# Balancing_Robot_1_2_Sensors.net
KiCad netlist of a schematic drawn in Altium Designer
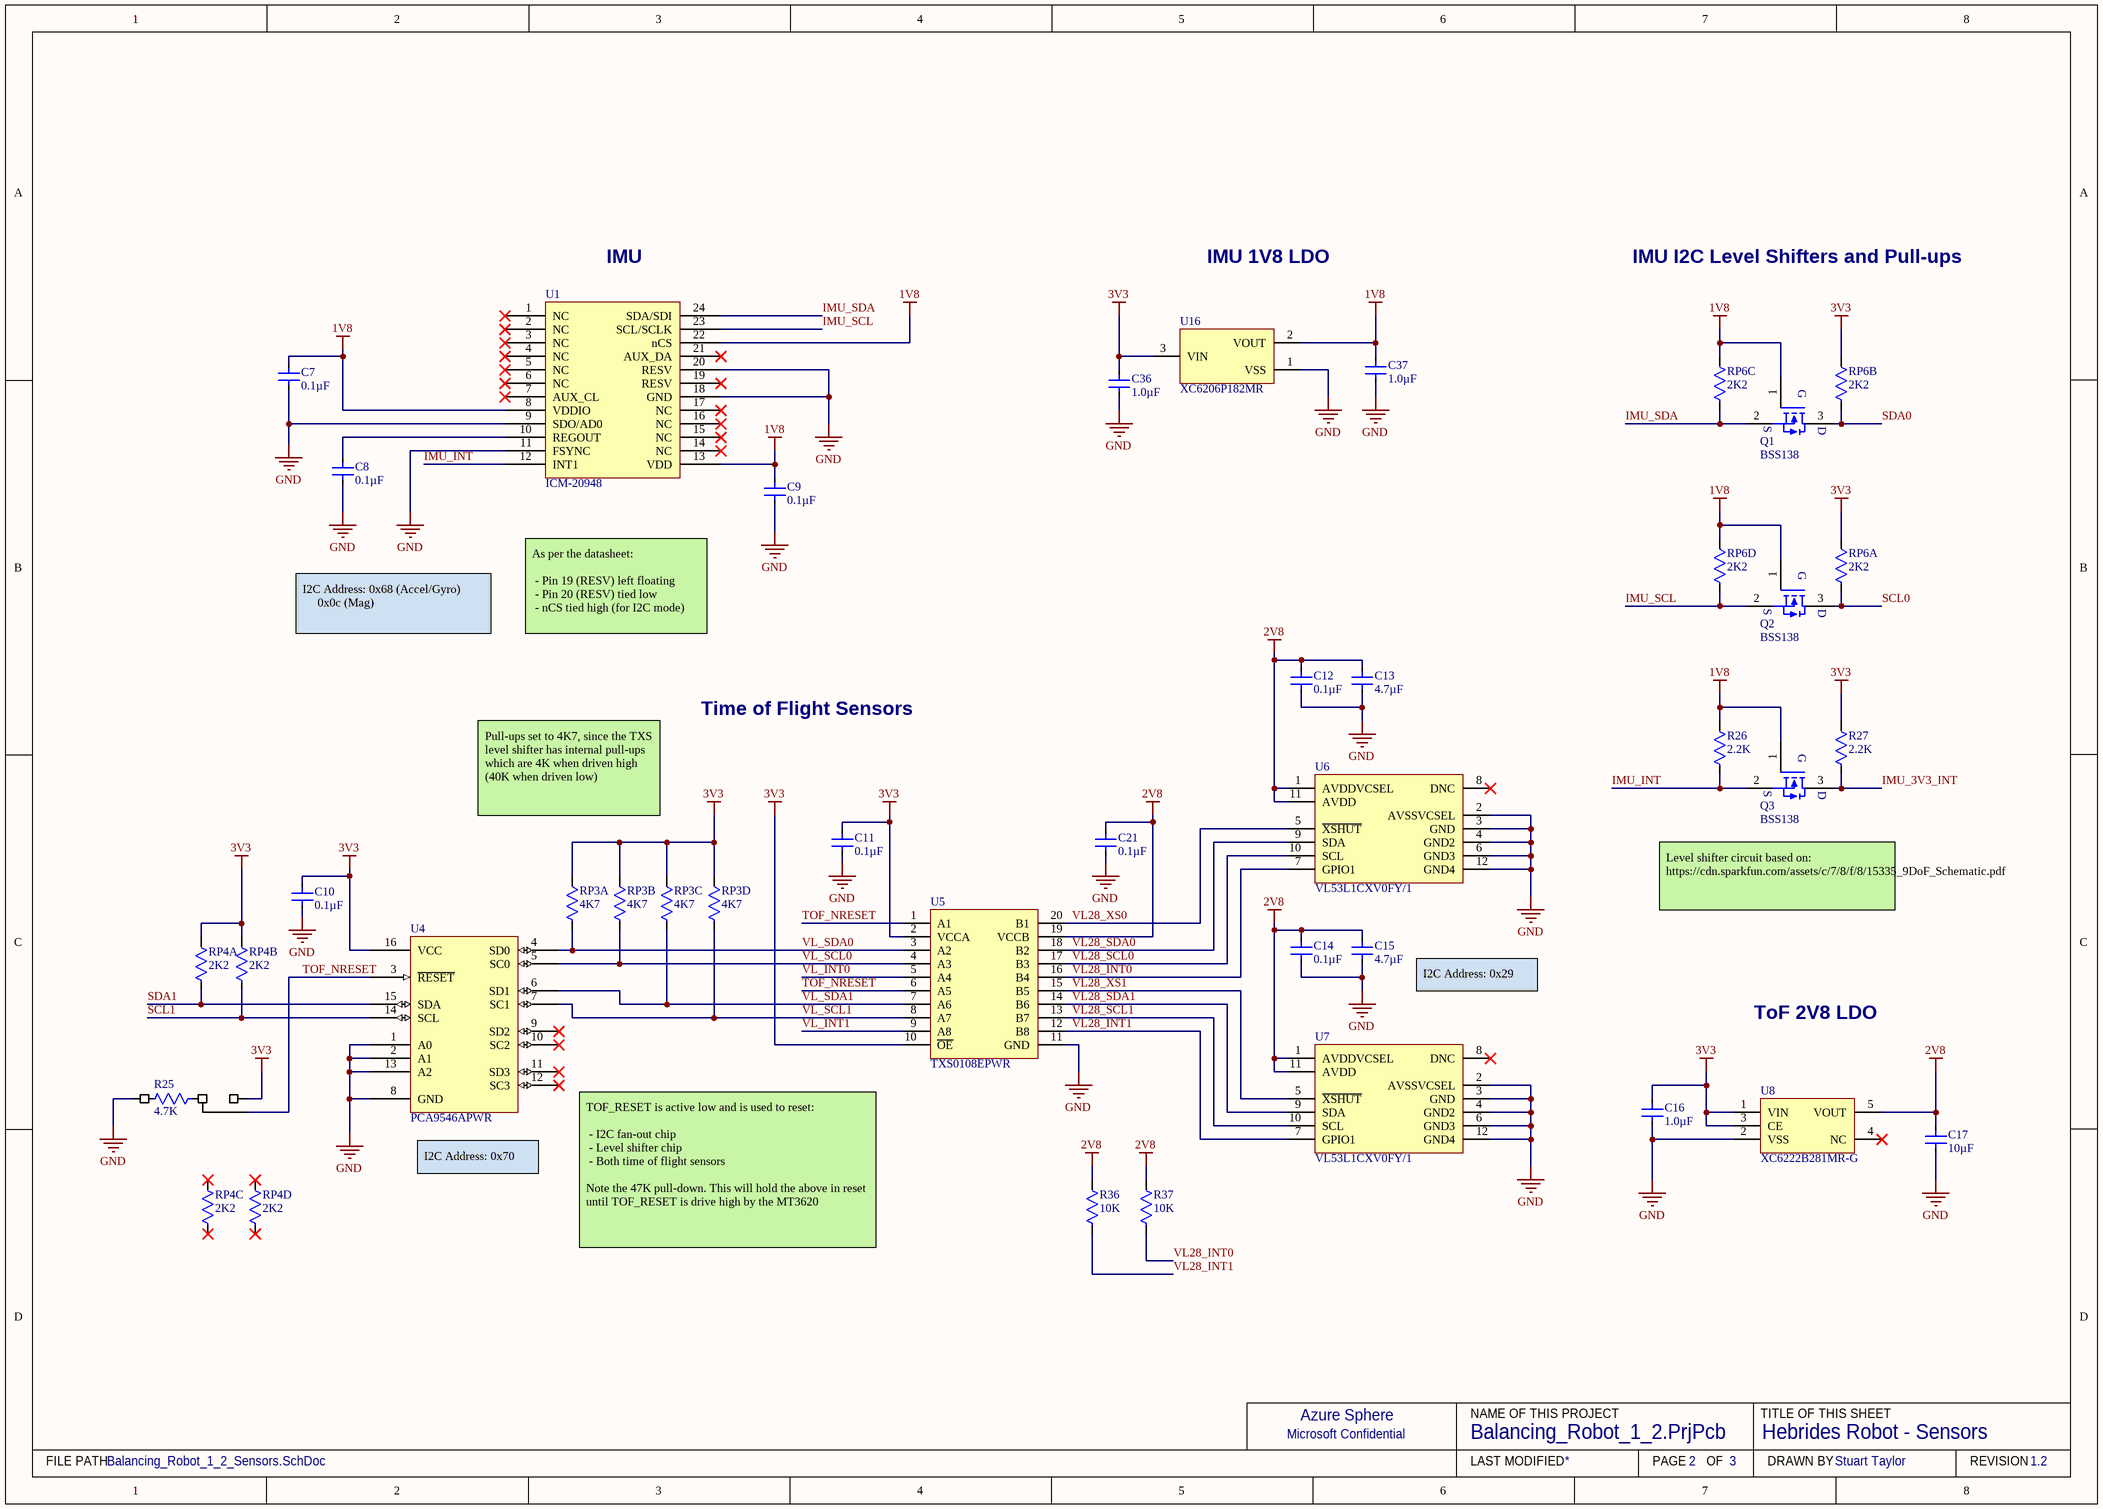
[diagram p0: Balancing_Robot_1_2_Sensors.SchDoc]

(export (version "E")
  (design (tool "Eeschema 10.0.6"))
  (components
    (comp (ref "C7")
      (value "0.1µF")
      (footprint "CAPC1005-EIA0402 0.55MM MED")
      (description "CAP CER 0.1UF 50V 10% X7R 0402")
      (fields
        (field (name "MANUFACTURER") "TDK Corporation")
        (field (name "MANUFACTURER PART NUMBER") "C1005X7R1H104K050BB")
        (field (name "CAPACITANCE") "0.1µF")
      )
      (libsource (lib "TDK_Capacitor_C_0402") (part "0.1µF 0402 X7R 50V"))
    )
    (comp (ref "C8")
      (value "0.1µF")
      (footprint "CAPC1005-EIA0402 0.55MM MED")
      (description "CAP CER 0.1UF 50V 10% X7R 0402")
      (fields
        (field (name "MANUFACTURER") "TDK Corporation")
        (field (name "MANUFACTURER PART NUMBER") "C1005X7R1H104K050BB")
        (field (name "CAPACITANCE") "0.1µF")
      )
      (libsource (lib "TDK_Capacitor_C_0402") (part "0.1µF 0402 X7R 50V"))
    )
    (comp (ref "C9")
      (value "0.1µF")
      (footprint "CAPC1005-EIA0402 0.55MM MED")
      (description "CAP CER 0.1UF 50V 10% X7R 0402")
      (fields
        (field (name "MANUFACTURER") "TDK Corporation")
        (field (name "MANUFACTURER PART NUMBER") "C1005X7R1H104K050BB")
        (field (name "CAPACITANCE") "0.1µF")
      )
      (libsource (lib "TDK_Capacitor_C_0402") (part "0.1µF 0402 X7R 50V"))
    )
    (comp (ref "C10")
      (value "0.1µF")
      (footprint "CAPC1005-EIA0402 0.55MM MED")
      (description "CAP CER 0.1UF 50V 10% X7R 0402")
      (fields
        (field (name "MANUFACTURER") "TDK Corporation")
        (field (name "MANUFACTURER PART NUMBER") "C1005X7R1H104K050BB")
        (field (name "CAPACITANCE") "0.1µF")
      )
      (libsource (lib "TDK_Capacitor_C_0402") (part "0.1µF 0402 X7R 50V"))
    )
    (comp (ref "C11")
      (value "0.1µF")
      (footprint "CAPC1005-EIA0402 0.55MM MED")
      (description "CAP CER 0.1UF 50V 10% X7R 0402")
      (fields
        (field (name "MANUFACTURER") "TDK Corporation")
        (field (name "MANUFACTURER PART NUMBER") "C1005X7R1H104K050BB")
        (field (name "CAPACITANCE") "0.1µF")
      )
      (libsource (lib "TDK_Capacitor_C_0402") (part "0.1µF 0402 X7R 50V"))
    )
    (comp (ref "C12")
      (value "0.1µF")
      (footprint "CAPC1005-EIA0402 0.55MM MED")
      (description "CAP CER 0.1UF 50V 10% X7R 0402")
      (fields
        (field (name "MANUFACTURER") "TDK Corporation")
        (field (name "MANUFACTURER PART NUMBER") "C1005X7R1H104K050BB")
        (field (name "CAPACITANCE") "0.1µF")
      )
      (libsource (lib "TDK_Capacitor_C_0402") (part "0.1µF 0402 X7R 50V"))
    )
    (comp (ref "C13")
      (value "C1005X5R1A475K050BC")
      (footprint "CAPC1005-EIA0402 0.55MM MED")
      (description "CAP CER 4.7UF 10V 10% X5R 0402")
      (fields
        (field (name "MANUFACTURER") "TDK Corporation")
        (field (name "TOLERANCE") "±10%")
        (field (name "CAPACITANCE") "4.7µF")
      )
      (libsource (lib "TDK_Capacitor_C_0402") (part "4.7µF 0402 X5R 10V"))
    )
    (comp (ref "C14")
      (value "0.1µF")
      (footprint "CAPC1005-EIA0402 0.55MM MED")
      (description "CAP CER 0.1UF 50V 10% X7R 0402")
      (fields
        (field (name "MANUFACTURER") "TDK Corporation")
        (field (name "MANUFACTURER PART NUMBER") "C1005X7R1H104K050BB")
        (field (name "CAPACITANCE") "0.1µF")
      )
      (libsource (lib "TDK_Capacitor_C_0402") (part "0.1µF 0402 X7R 50V"))
    )
    (comp (ref "C15")
      (value "C1005X5R1A475K050BC")
      (footprint "CAPC1005-EIA0402 0.55MM MED")
      (description "CAP CER 4.7UF 10V 10% X5R 0402")
      (fields
        (field (name "MANUFACTURER") "TDK Corporation")
        (field (name "TOLERANCE") "±10%")
        (field (name "CAPACITANCE") "4.7µF")
      )
      (libsource (lib "TDK_Capacitor_C_0402") (part "4.7µF 0402 X5R 10V"))
    )
    (comp (ref "C16")
      (value "C1005X5R1V105K050BC")
      (footprint "CAPC1005-EIA0402 0.55MM MED")
      (description "CAP CER 1UF 35V 10% X5R 0402")
      (fields
        (field (name "MANUFACTURER") "TDK Corporation")
        (field (name "TOLERANCE") "±10%")
        (field (name "CAPACITANCE") "1.0µF")
      )
      (libsource (lib "TDK_Capacitor_C_0402") (part "1.0µF 0402 X5R 35V"))
    )
    (comp (ref "C17")
      (value "10µF")
      (footprint "CAPC1005-EIA0402 0.55MM MED")
      (description "CAP CER 10UF 6.3V 20% X5R 0402")
      (fields
        (field (name "MANUFACTURER") "TDK Corporation")
        (field (name "MANUFACTURER PART NUMBER") "C1005X5R0J106M050BC")
        (field (name "CAPACITANCE") "10µF")
      )
      (libsource (lib "TDK_Capacitor_C_0402") (part "10µF 0402 X5R 6.3V"))
    )
    (comp (ref "C21")
      (value "0.1µF")
      (footprint "CAPC1005-EIA0402 0.55MM MED")
      (description "CAP CER 0.1UF 50V 10% X7R 0402")
      (fields
        (field (name "MANUFACTURER") "TDK Corporation")
        (field (name "MANUFACTURER PART NUMBER") "C1005X7R1H104K050BB")
        (field (name "CAPACITANCE") "0.1µF")
      )
      (libsource (lib "TDK_Capacitor_C_0402") (part "0.1µF 0402 X7R 50V"))
    )
    (comp (ref "C36")
      (value "C1005X5R1V105K050BC")
      (footprint "CAPC1005-EIA0402 0.55MM MED")
      (description "CAP CER 1UF 35V 10% X5R 0402")
      (fields
        (field (name "MANUFACTURER") "TDK Corporation")
        (field (name "TOLERANCE") "±10%")
        (field (name "CAPACITANCE") "1.0µF")
      )
      (libsource (lib "TDK_Capacitor_C_0402") (part "1.0µF 0402 X5R 35V"))
    )
    (comp (ref "C37")
      (value "C1005X5R1V105K050BC")
      (footprint "CAPC1005-EIA0402 0.55MM MED")
      (description "CAP CER 1UF 35V 10% X5R 0402")
      (fields
        (field (name "MANUFACTURER") "TDK Corporation")
        (field (name "TOLERANCE") "±10%")
        (field (name "CAPACITANCE") "1.0µF")
      )
      (libsource (lib "TDK_Capacitor_C_0402") (part "1.0µF 0402 X5R 35V"))
    )
    (comp (ref "Q1")
      (value "BSS138")
      (footprint "TOREX-SOT23-3")
      (description "MOSFET N-CH 50V 220MA SOT-23")
      (fields (field (name "MANUFACTURER") "Micross"))
      (libsource (lib "Fairchild") (part "BSS138"))
    )
    (comp (ref "Q2")
      (value "BSS138")
      (footprint "TOREX-SOT23-3")
      (description "MOSFET N-CH 50V 220MA SOT-23")
      (fields (field (name "MANUFACTURER") "Micross"))
      (libsource (lib "Fairchild") (part "BSS138"))
    )
    (comp (ref "Q3")
      (value "BSS138")
      (footprint "TOREX-SOT23-3")
      (description "MOSFET N-CH 50V 220MA SOT-23")
      (fields (field (name "MANUFACTURER") "Micross"))
      (libsource (lib "Fairchild") (part "BSS138"))
    )
    (comp (ref "R25")
      (value "4.7K")
      (footprint "THREE-WAY-0402-NO-SHORT")
      (description "RES SMD 4.7K JUMPER 1/10W 0402")
      (fields
        (field (name "MANUFACTURER") "Panasonic Electronic Components")
        (field (name "MANUFACTURER PART NUMBER") "ERJ-2RKF4701X")
      )
      (libsource (lib "generic-res") (part "THREE-WAY-4K7-0402-NO-SHORT"))
    )
    (comp (ref "R26")
      (value "2.2K")
      (footprint "RES 0402 MEDIUM DENSITY")
      (description "RES 2.2K OHM 1/10W 1% 0402 SMD")
      (fields
        (field (name "MANUFACTURER") "Panasonic Electronic Components")
        (field (name "MANUFACTURER PART NUMBER") "ERJ-2RKF2201X")
        (field (name "RESISTANCE (OHMS)") "2.2K")
      )
      (libsource (lib "Panasonic_Resistor_ERJ2R") (part "2.2K"))
    )
    (comp (ref "R27")
      (value "2.2K")
      (footprint "RES 0402 MEDIUM DENSITY")
      (description "RES 2.2K OHM 1/10W 1% 0402 SMD")
      (fields
        (field (name "MANUFACTURER") "Panasonic Electronic Components")
        (field (name "MANUFACTURER PART NUMBER") "ERJ-2RKF2201X")
        (field (name "RESISTANCE (OHMS)") "2.2K")
      )
      (libsource (lib "Panasonic_Resistor_ERJ2R") (part "2.2K"))
    )
    (comp (ref "R36")
      (value "10K")
      (footprint "RES 0402 MEDIUM DENSITY")
      (description "RES 10K OHM 1/10W 1% 0402 SMD")
      (fields
        (field (name "MANUFACTURER") "Panasonic Electronic Components")
        (field (name "MANUFACTURER PART NUMBER") "ERJ-2RKF1002X")
        (field (name "RESISTANCE (OHMS)") "10K")
      )
      (libsource (lib "Panasonic_Resistor_ERJ2R") (part "10K"))
    )
    (comp (ref "R37")
      (value "10K")
      (footprint "RES 0402 MEDIUM DENSITY")
      (description "RES 10K OHM 1/10W 1% 0402 SMD")
      (fields
        (field (name "MANUFACTURER") "Panasonic Electronic Components")
        (field (name "MANUFACTURER PART NUMBER") "ERJ-2RKF1002X")
        (field (name "RESISTANCE (OHMS)") "10K")
      )
      (libsource (lib "Panasonic_Resistor_ERJ2R") (part "10K"))
    )
    (comp (ref "RP3")
      (value "4K7")
      (footprint "EXB-N8V")
      (fields
        (field (name "MANUFACTURER") "Panasonic / Panasonic ECG")
        (field (name "MANUFACTURER PART NUMBER") "EXB-N8V472JX")
      )
      (libsource (lib "Panasonic") (part "EXB-N8V472JX"))
    )
    (comp (ref "RP4")
      (value "2K2")
      (footprint "EXB-N8V")
      (fields
        (field (name "MANUFACTURER") "Panasonic / Panasonic ECG")
        (field (name "MANUFACTURER PART NUMBER") "EXB-N8V222JX")
      )
      (libsource (lib "Panasonic") (part "EXB-N8V222JX"))
    )
    (comp (ref "RP6")
      (value "2K2")
      (footprint "EXB-N8V")
      (fields
        (field (name "MANUFACTURER") "Panasonic / Panasonic ECG")
        (field (name "MANUFACTURER PART NUMBER") "EXB-N8V222JX")
      )
      (libsource (lib "Panasonic") (part "EXB-N8V222JX"))
    )
    (comp (ref "U1")
      (value "ICM-20948")
      (footprint "ICM_20948")
      (description "9-axis IMU")
      (fields (field (name "MANUFACTURER") "TDK"))
      (libsource (lib "InvenSense") (part "ICM-20948"))
    )
    (comp (ref "U4")
      (value "PCA9546APWR")
      (footprint "PCA9546APWR")
      (fields (field (name "MANUFACTURER") "Texas Instruments"))
      (libsource (lib "TexasInstruments") (part "PCA9546APWR"))
    )
    (comp (ref "U5")
      (value "TXS0108EPWR")
      (footprint "TXS0108EPWR")
      (description "IC 8BIT NON-INV TRANSLTR 20TSSOP")
      (fields (field (name "MANUFACTURER") "Texas Instruments"))
      (libsource (lib "TexasInstruments") (part "TXS0108EPWR"))
    )
    (comp (ref "U6")
      (value "VL53L1CXV0FY/1")
      (footprint "VL53L1X")
      (description "OPTICAL LGA12 4.9X2")
      (fields (field (name "MANUFACTURER") "STMicroelectronics"))
      (libsource (lib "ST") (part "VL53L1CXV0FY/1"))
    )
    (comp (ref "U7")
      (value "VL53L1CXV0FY/1")
      (footprint "VL53L1X")
      (description "OPTICAL LGA12 4.9X2")
      (fields (field (name "MANUFACTURER") "STMicroelectronics"))
      (libsource (lib "ST") (part "VL53L1CXV0FY/1"))
    )
    (comp (ref "U8")
      (value "XC6222B281MR-G")
      (footprint "SOT25")
      (description "Reverse Current Protection, 700mA High Speed LDO Regulator")
      (fields (field (name "MANUFACTURER") "Torex"))
      (libsource (lib "Torex") (part "XC6222B281MR-G"))
    )
    (comp (ref "U16")
      (value "XC6206P182MR")
      (footprint "TOREX-SOT23-3")
      (fields (field (name "MANUFACTURER") "Torex Semiconductor"))
      (libsource (lib "Torex") (part "XC6206P182MR"))
    )
  )
  (nets
    (net (code "1") (name "/IMU_3V3_INT") (class "Default")
      (node (ref "Q3") (pin "3") (pinfunction "D_3") (pintype "passive"))
      (node (ref "R27") (pin "2") (pinfunction "2_2") (pintype "passive"))
    )
    (net (code "2") (name "/IMU_INT") (class "Default")
      (node (ref "Q3") (pin "2") (pinfunction "S_2") (pintype "passive"))
      (node (ref "R26") (pin "2") (pinfunction "2_2") (pintype "passive"))
      (node (ref "U1") (pin "12") (pinfunction "INT1_12") (pintype "passive"))
    )
    (net (code "3") (name "/IMU_SCL") (class "Default")
      (node (ref "Q2") (pin "2") (pinfunction "S_2") (pintype "passive"))
      (node (ref "RP6") (pin "7") (pinfunction "7_7") (pintype "passive"))
      (node (ref "U1") (pin "23") (pinfunction "SCL/SCLK_23") (pintype "passive"))
    )
    (net (code "4") (name "/IMU_SDA") (class "Default")
      (node (ref "Q1") (pin "2") (pinfunction "S_2") (pintype "passive"))
      (node (ref "RP6") (pin "5") (pinfunction "5_5") (pintype "passive"))
      (node (ref "U1") (pin "24") (pinfunction "SDA/SDI_24") (pintype "passive"))
    )
    (net (code "5") (name "/SCL0") (class "Default")
      (node (ref "Q2") (pin "3") (pinfunction "D_3") (pintype "passive"))
      (node (ref "RP6") (pin "1") (pinfunction "1_1") (pintype "passive"))
    )
    (net (code "6") (name "/SCL1") (class "Default")
      (node (ref "RP4") (pin "3") (pinfunction "3_3") (pintype "passive"))
      (node (ref "U4") (pin "14") (pinfunction "SCL_14") (pintype "bidirectional"))
    )
    (net (code "7") (name "/SDA0") (class "Default")
      (node (ref "Q1") (pin "3") (pinfunction "D_3") (pintype "passive"))
      (node (ref "RP6") (pin "3") (pinfunction "3_3") (pintype "passive"))
    )
    (net (code "8") (name "/SDA1") (class "Default")
      (node (ref "RP4") (pin "1") (pinfunction "1_1") (pintype "passive"))
      (node (ref "U4") (pin "15") (pinfunction "SDA_15") (pintype "bidirectional"))
    )
    (net (code "9") (name "/TOF_NRESET") (class "Default")
      (node (ref "R25") (pin "2") (pinfunction "2_2") (pintype "passive"))
      (node (ref "U4") (pin "3") (pinfunction "~{RESET}_3") (pintype "input"))
      (node (ref "U5") (pin "1") (pinfunction "A1_1") (pintype "passive"))
      (node (ref "U5") (pin "6") (pinfunction "A5_6") (pintype "passive"))
    )
    (net (code "10") (name "/VL28_INT0") (class "Default")
      (node (ref "R37") (pin "2") (pinfunction "2_2") (pintype "passive"))
      (node (ref "U5") (pin "16") (pinfunction "B4_16") (pintype "passive"))
      (node (ref "U6") (pin "7") (pinfunction "GPIO1_7") (pintype "passive"))
    )
    (net (code "11") (name "/VL28_INT1") (class "Default")
      (node (ref "R36") (pin "2") (pinfunction "2_2") (pintype "passive"))
      (node (ref "U5") (pin "12") (pinfunction "B8_12") (pintype "passive"))
      (node (ref "U7") (pin "7") (pinfunction "GPIO1_7") (pintype "passive"))
    )
    (net (code "12") (name "/VL28_SCL0") (class "Default")
      (node (ref "U5") (pin "17") (pinfunction "B3_17") (pintype "passive"))
      (node (ref "U6") (pin "10") (pinfunction "SCL_10") (pintype "passive"))
    )
    (net (code "13") (name "/VL28_SCL1") (class "Default")
      (node (ref "U5") (pin "13") (pinfunction "B7_13") (pintype "passive"))
      (node (ref "U7") (pin "10") (pinfunction "SCL_10") (pintype "passive"))
    )
    (net (code "14") (name "/VL28_SDA0") (class "Default")
      (node (ref "U5") (pin "18") (pinfunction "B2_18") (pintype "passive"))
      (node (ref "U6") (pin "9") (pinfunction "SDA_9") (pintype "passive"))
    )
    (net (code "15") (name "/VL28_SDA1") (class "Default")
      (node (ref "U5") (pin "14") (pinfunction "B6_14") (pintype "passive"))
      (node (ref "U7") (pin "9") (pinfunction "SDA_9") (pintype "passive"))
    )
    (net (code "16") (name "/VL28_XS0") (class "Default")
      (node (ref "U5") (pin "20") (pinfunction "B1_20") (pintype "passive"))
      (node (ref "U6") (pin "5") (pinfunction "~{XSHUT}_5") (pintype "passive"))
    )
    (net (code "17") (name "/VL28_XS1") (class "Default")
      (node (ref "U5") (pin "15") (pinfunction "B5_15") (pintype "passive"))
      (node (ref "U7") (pin "5") (pinfunction "~{XSHUT}_5") (pintype "passive"))
    )
    (net (code "18") (name "/VL_INT0") (class "Default")
      (node (ref "U5") (pin "5") (pinfunction "A4_5") (pintype "passive"))
    )
    (net (code "19") (name "/VL_INT1") (class "Default")
      (node (ref "U5") (pin "9") (pinfunction "A8_9") (pintype "passive"))
    )
    (net (code "20") (name "/VL_SCL0") (class "Default")
      (node (ref "RP3") (pin "3") (pinfunction "3_3") (pintype "passive"))
      (node (ref "U4") (pin "5") (pinfunction "SC0_5") (pintype "bidirectional"))
      (node (ref "U5") (pin "4") (pinfunction "A3_4") (pintype "passive"))
    )
    (net (code "21") (name "/VL_SCL1") (class "Default")
      (node (ref "RP3") (pin "7") (pinfunction "7_7") (pintype "passive"))
      (node (ref "U4") (pin "7") (pinfunction "SC1_7") (pintype "bidirectional"))
      (node (ref "U5") (pin "8") (pinfunction "A7_8") (pintype "passive"))
    )
    (net (code "22") (name "/VL_SDA0") (class "Default")
      (node (ref "RP3") (pin "1") (pinfunction "1_1") (pintype "passive"))
      (node (ref "U4") (pin "4") (pinfunction "SD0_4") (pintype "bidirectional"))
      (node (ref "U5") (pin "3") (pinfunction "A2_3") (pintype "passive"))
    )
    (net (code "23") (name "/VL_SDA1") (class "Default")
      (node (ref "RP3") (pin "5") (pinfunction "5_5") (pintype "passive"))
      (node (ref "U4") (pin "6") (pinfunction "SD1_6") (pintype "bidirectional"))
      (node (ref "U5") (pin "7") (pinfunction "A6_7") (pintype "passive"))
    )
    (net (code "24") (name "1V8") (class "Default")
      (node (ref "C37") (pin "2") (pinfunction "2_2") (pintype "passive"))
      (node (ref "C7") (pin "2") (pinfunction "2_2") (pintype "passive"))
      (node (ref "C9") (pin "2") (pinfunction "2_2") (pintype "passive"))
      (node (ref "Q1") (pin "1") (pinfunction "G_1") (pintype "passive"))
      (node (ref "Q2") (pin "1") (pinfunction "G_1") (pintype "passive"))
      (node (ref "Q3") (pin "1") (pinfunction "G_1") (pintype "passive"))
      (node (ref "R26") (pin "1") (pinfunction "1_1") (pintype "passive"))
      (node (ref "RP6") (pin "6") (pinfunction "6_6") (pintype "passive"))
      (node (ref "RP6") (pin "8") (pinfunction "8_8") (pintype "passive"))
      (node (ref "U1") (pin "13") (pinfunction "VDD_13") (pintype "passive"))
      (node (ref "U1") (pin "22") (pinfunction "nCS_22") (pintype "passive"))
      (node (ref "U1") (pin "8") (pinfunction "VDDIO_8") (pintype "passive"))
      (node (ref "U16") (pin "2") (pinfunction "VOUT_2") (pintype "passive"))
    )
    (net (code "25") (name "2V8") (class "Default")
      (node (ref "C12") (pin "2") (pinfunction "2_2") (pintype "passive"))
      (node (ref "C13") (pin "2") (pinfunction "2_2") (pintype "passive"))
      (node (ref "C14") (pin "2") (pinfunction "2_2") (pintype "passive"))
      (node (ref "C15") (pin "2") (pinfunction "2_2") (pintype "passive"))
      (node (ref "C17") (pin "2") (pinfunction "2_2") (pintype "passive"))
      (node (ref "C21") (pin "2") (pinfunction "2_2") (pintype "passive"))
      (node (ref "R36") (pin "1") (pinfunction "1_1") (pintype "passive"))
      (node (ref "R37") (pin "1") (pinfunction "1_1") (pintype "passive"))
      (node (ref "U5") (pin "19") (pinfunction "VCCB_19") (pintype "passive"))
      (node (ref "U6") (pin "1") (pinfunction "AVDDVCSEL_1") (pintype "passive"))
      (node (ref "U6") (pin "11") (pinfunction "AVDD_11") (pintype "passive"))
      (node (ref "U7") (pin "1") (pinfunction "AVDDVCSEL_1") (pintype "passive"))
      (node (ref "U7") (pin "11") (pinfunction "AVDD_11") (pintype "passive"))
      (node (ref "U8") (pin "5") (pinfunction "VOUT_5") (pintype "passive"))
    )
    (net (code "26") (name "3V3") (class "Default")
      (node (ref "C10") (pin "2") (pinfunction "2_2") (pintype "passive"))
      (node (ref "C11") (pin "2") (pinfunction "2_2") (pintype "passive"))
      (node (ref "C16") (pin "2") (pinfunction "2_2") (pintype "passive"))
      (node (ref "C36") (pin "2") (pinfunction "2_2") (pintype "passive"))
      (node (ref "R25") (pin "3") (pinfunction "3_3") (pintype "passive"))
      (node (ref "R27") (pin "1") (pinfunction "1_1") (pintype "passive"))
      (node (ref "RP3") (pin "2") (pinfunction "2_2") (pintype "passive"))
      (node (ref "RP3") (pin "4") (pinfunction "4_4") (pintype "passive"))
      (node (ref "RP3") (pin "6") (pinfunction "6_6") (pintype "passive"))
      (node (ref "RP3") (pin "8") (pinfunction "8_8") (pintype "passive"))
      (node (ref "RP4") (pin "2") (pinfunction "2_2") (pintype "passive"))
      (node (ref "RP4") (pin "4") (pinfunction "4_4") (pintype "passive"))
      (node (ref "RP6") (pin "2") (pinfunction "2_2") (pintype "passive"))
      (node (ref "RP6") (pin "4") (pinfunction "4_4") (pintype "passive"))
      (node (ref "U16") (pin "3") (pinfunction "VIN_3") (pintype "passive"))
      (node (ref "U4") (pin "16") (pinfunction "VCC_16") (pintype "power_in"))
      (node (ref "U5") (pin "10") (pinfunction "~{OE}_10") (pintype "passive"))
      (node (ref "U5") (pin "2") (pinfunction "VCCA_2") (pintype "passive"))
      (node (ref "U8") (pin "1") (pinfunction "VIN_1") (pintype "passive"))
      (node (ref "U8") (pin "3") (pinfunction "CE_3") (pintype "passive"))
    )
    (net (code "27") (name "GND") (class "Default")
      (node (ref "C10") (pin "1") (pinfunction "1_1") (pintype "passive"))
      (node (ref "C11") (pin "1") (pinfunction "1_1") (pintype "passive"))
      (node (ref "C12") (pin "1") (pinfunction "1_1") (pintype "passive"))
      (node (ref "C13") (pin "1") (pinfunction "1_1") (pintype "passive"))
      (node (ref "C14") (pin "1") (pinfunction "1_1") (pintype "passive"))
      (node (ref "C15") (pin "1") (pinfunction "1_1") (pintype "passive"))
      (node (ref "C16") (pin "1") (pinfunction "1_1") (pintype "passive"))
      (node (ref "C17") (pin "1") (pinfunction "1_1") (pintype "passive"))
      (node (ref "C21") (pin "1") (pinfunction "1_1") (pintype "passive"))
      (node (ref "C36") (pin "1") (pinfunction "1_1") (pintype "passive"))
      (node (ref "C37") (pin "1") (pinfunction "1_1") (pintype "passive"))
      (node (ref "C7") (pin "1") (pinfunction "1_1") (pintype "passive"))
      (node (ref "C8") (pin "1") (pinfunction "1_1") (pintype "passive"))
      (node (ref "C9") (pin "1") (pinfunction "1_1") (pintype "passive"))
      (node (ref "R25") (pin "1") (pinfunction "1_1") (pintype "passive"))
      (node (ref "U1") (pin "11") (pinfunction "FSYNC_11") (pintype "passive"))
      (node (ref "U1") (pin "18") (pinfunction "GND_18") (pintype "passive"))
      (node (ref "U1") (pin "20") (pinfunction "RESV_20") (pintype "passive"))
      (node (ref "U1") (pin "9") (pinfunction "SDO/AD0_9") (pintype "passive"))
      (node (ref "U16") (pin "1") (pinfunction "VSS_1") (pintype "passive"))
      (node (ref "U4") (pin "1") (pinfunction "A0_1") (pintype "power_in"))
      (node (ref "U4") (pin "13") (pinfunction "A2_13") (pintype "power_in"))
      (node (ref "U4") (pin "2") (pinfunction "A1_2") (pintype "power_in"))
      (node (ref "U4") (pin "8") (pinfunction "GND_8") (pintype "power_in"))
      (node (ref "U5") (pin "11") (pinfunction "GND_11") (pintype "passive"))
      (node (ref "U6") (pin "12") (pinfunction "GND4_12") (pintype "passive"))
      (node (ref "U6") (pin "2") (pinfunction "AVSSVCSEL_2") (pintype "passive"))
      (node (ref "U6") (pin "3") (pinfunction "GND_3") (pintype "passive"))
      (node (ref "U6") (pin "4") (pinfunction "GND2_4") (pintype "passive"))
      (node (ref "U6") (pin "6") (pinfunction "GND3_6") (pintype "passive"))
      (node (ref "U7") (pin "12") (pinfunction "GND4_12") (pintype "passive"))
      (node (ref "U7") (pin "2") (pinfunction "AVSSVCSEL_2") (pintype "passive"))
      (node (ref "U7") (pin "3") (pinfunction "GND_3") (pintype "passive"))
      (node (ref "U7") (pin "4") (pinfunction "GND2_4") (pintype "passive"))
      (node (ref "U7") (pin "6") (pinfunction "GND3_6") (pintype "passive"))
      (node (ref "U8") (pin "2") (pinfunction "VSS_2") (pintype "passive"))
    )
    (net (code "28") (name "Net-(U1-REGOUT)") (class "Default")
      (node (ref "C8") (pin "2") (pinfunction "2_2") (pintype "passive"))
      (node (ref "U1") (pin "10") (pinfunction "REGOUT_10") (pintype "passive"))
    )
    (net (code "29") (name "unconnected-(RP4-Pad5)") (class "Default")
      (node (ref "RP4") (pin "5") (pinfunction "5_5") (pintype "passive+no_connect"))
    )
    (net (code "30") (name "unconnected-(RP4-Pad6)") (class "Default")
      (node (ref "RP4") (pin "6") (pinfunction "6_6") (pintype "passive+no_connect"))
    )
    (net (code "31") (name "unconnected-(RP4-Pad7)") (class "Default")
      (node (ref "RP4") (pin "7") (pinfunction "7_7") (pintype "passive+no_connect"))
    )
    (net (code "32") (name "unconnected-(RP4-Pad8)") (class "Default")
      (node (ref "RP4") (pin "8") (pinfunction "8_8") (pintype "passive+no_connect"))
    )
    (net (code "33") (name "unconnected-(U1-AUX_CL-Pad7)") (class "Default")
      (node (ref "U1") (pin "7") (pinfunction "AUX_CL_7") (pintype "passive+no_connect"))
    )
    (net (code "34") (name "unconnected-(U1-AUX_DA-Pad21)") (class "Default")
      (node (ref "U1") (pin "21") (pinfunction "AUX_DA_21") (pintype "passive+no_connect"))
    )
    (net (code "35") (name "unconnected-(U1-NC-Pad1)") (class "Default")
      (node (ref "U1") (pin "1") (pinfunction "NC_1") (pintype "passive+no_connect"))
    )
    (net (code "36") (name "unconnected-(U1-NC-Pad2)") (class "Default")
      (node (ref "U1") (pin "2") (pinfunction "NC_2") (pintype "passive+no_connect"))
    )
    (net (code "37") (name "unconnected-(U1-NC-Pad3)") (class "Default")
      (node (ref "U1") (pin "3") (pinfunction "NC_3") (pintype "passive+no_connect"))
    )
    (net (code "38") (name "unconnected-(U1-NC-Pad4)") (class "Default")
      (node (ref "U1") (pin "4") (pinfunction "NC_4") (pintype "passive+no_connect"))
    )
    (net (code "39") (name "unconnected-(U1-NC-Pad5)") (class "Default")
      (node (ref "U1") (pin "5") (pinfunction "NC_5") (pintype "passive+no_connect"))
    )
    (net (code "40") (name "unconnected-(U1-NC-Pad6)") (class "Default")
      (node (ref "U1") (pin "6") (pinfunction "NC_6") (pintype "passive+no_connect"))
    )
    (net (code "41") (name "unconnected-(U1-NC-Pad14)") (class "Default")
      (node (ref "U1") (pin "14") (pinfunction "NC_14") (pintype "passive+no_connect"))
    )
    (net (code "42") (name "unconnected-(U1-NC-Pad15)") (class "Default")
      (node (ref "U1") (pin "15") (pinfunction "NC_15") (pintype "passive+no_connect"))
    )
    (net (code "43") (name "unconnected-(U1-NC-Pad16)") (class "Default")
      (node (ref "U1") (pin "16") (pinfunction "NC_16") (pintype "passive+no_connect"))
    )
    (net (code "44") (name "unconnected-(U1-NC-Pad17)") (class "Default")
      (node (ref "U1") (pin "17") (pinfunction "NC_17") (pintype "passive+no_connect"))
    )
    (net (code "45") (name "unconnected-(U1-RESV-Pad19)") (class "Default")
      (node (ref "U1") (pin "19") (pinfunction "RESV_19") (pintype "passive+no_connect"))
    )
    (net (code "46") (name "unconnected-(U4-SC2-Pad10)") (class "Default")
      (node (ref "U4") (pin "10") (pinfunction "SC2_10") (pintype "bidirectional+no_connect"))
    )
    (net (code "47") (name "unconnected-(U4-SC3-Pad12)") (class "Default")
      (node (ref "U4") (pin "12") (pinfunction "SC3_12") (pintype "bidirectional+no_connect"))
    )
    (net (code "48") (name "unconnected-(U4-SD2-Pad9)") (class "Default")
      (node (ref "U4") (pin "9") (pinfunction "SD2_9") (pintype "bidirectional+no_connect"))
    )
    (net (code "49") (name "unconnected-(U4-SD3-Pad11)") (class "Default")
      (node (ref "U4") (pin "11") (pinfunction "SD3_11") (pintype "bidirectional+no_connect"))
    )
    (net (code "50") (name "unconnected-(U6-DNC-Pad8)") (class "Default")
      (node (ref "U6") (pin "8") (pinfunction "DNC_8") (pintype "passive+no_connect"))
    )
    (net (code "51") (name "unconnected-(U7-DNC-Pad8)") (class "Default")
      (node (ref "U7") (pin "8") (pinfunction "DNC_8") (pintype "passive+no_connect"))
    )
    (net (code "52") (name "unconnected-(U8-NC-Pad4)") (class "Default")
      (node (ref "U8") (pin "4") (pinfunction "NC_4") (pintype "passive+no_connect"))
    )
  )
)
